# Micro.net
KiCad netlist of a schematic drawn in Altium Designer
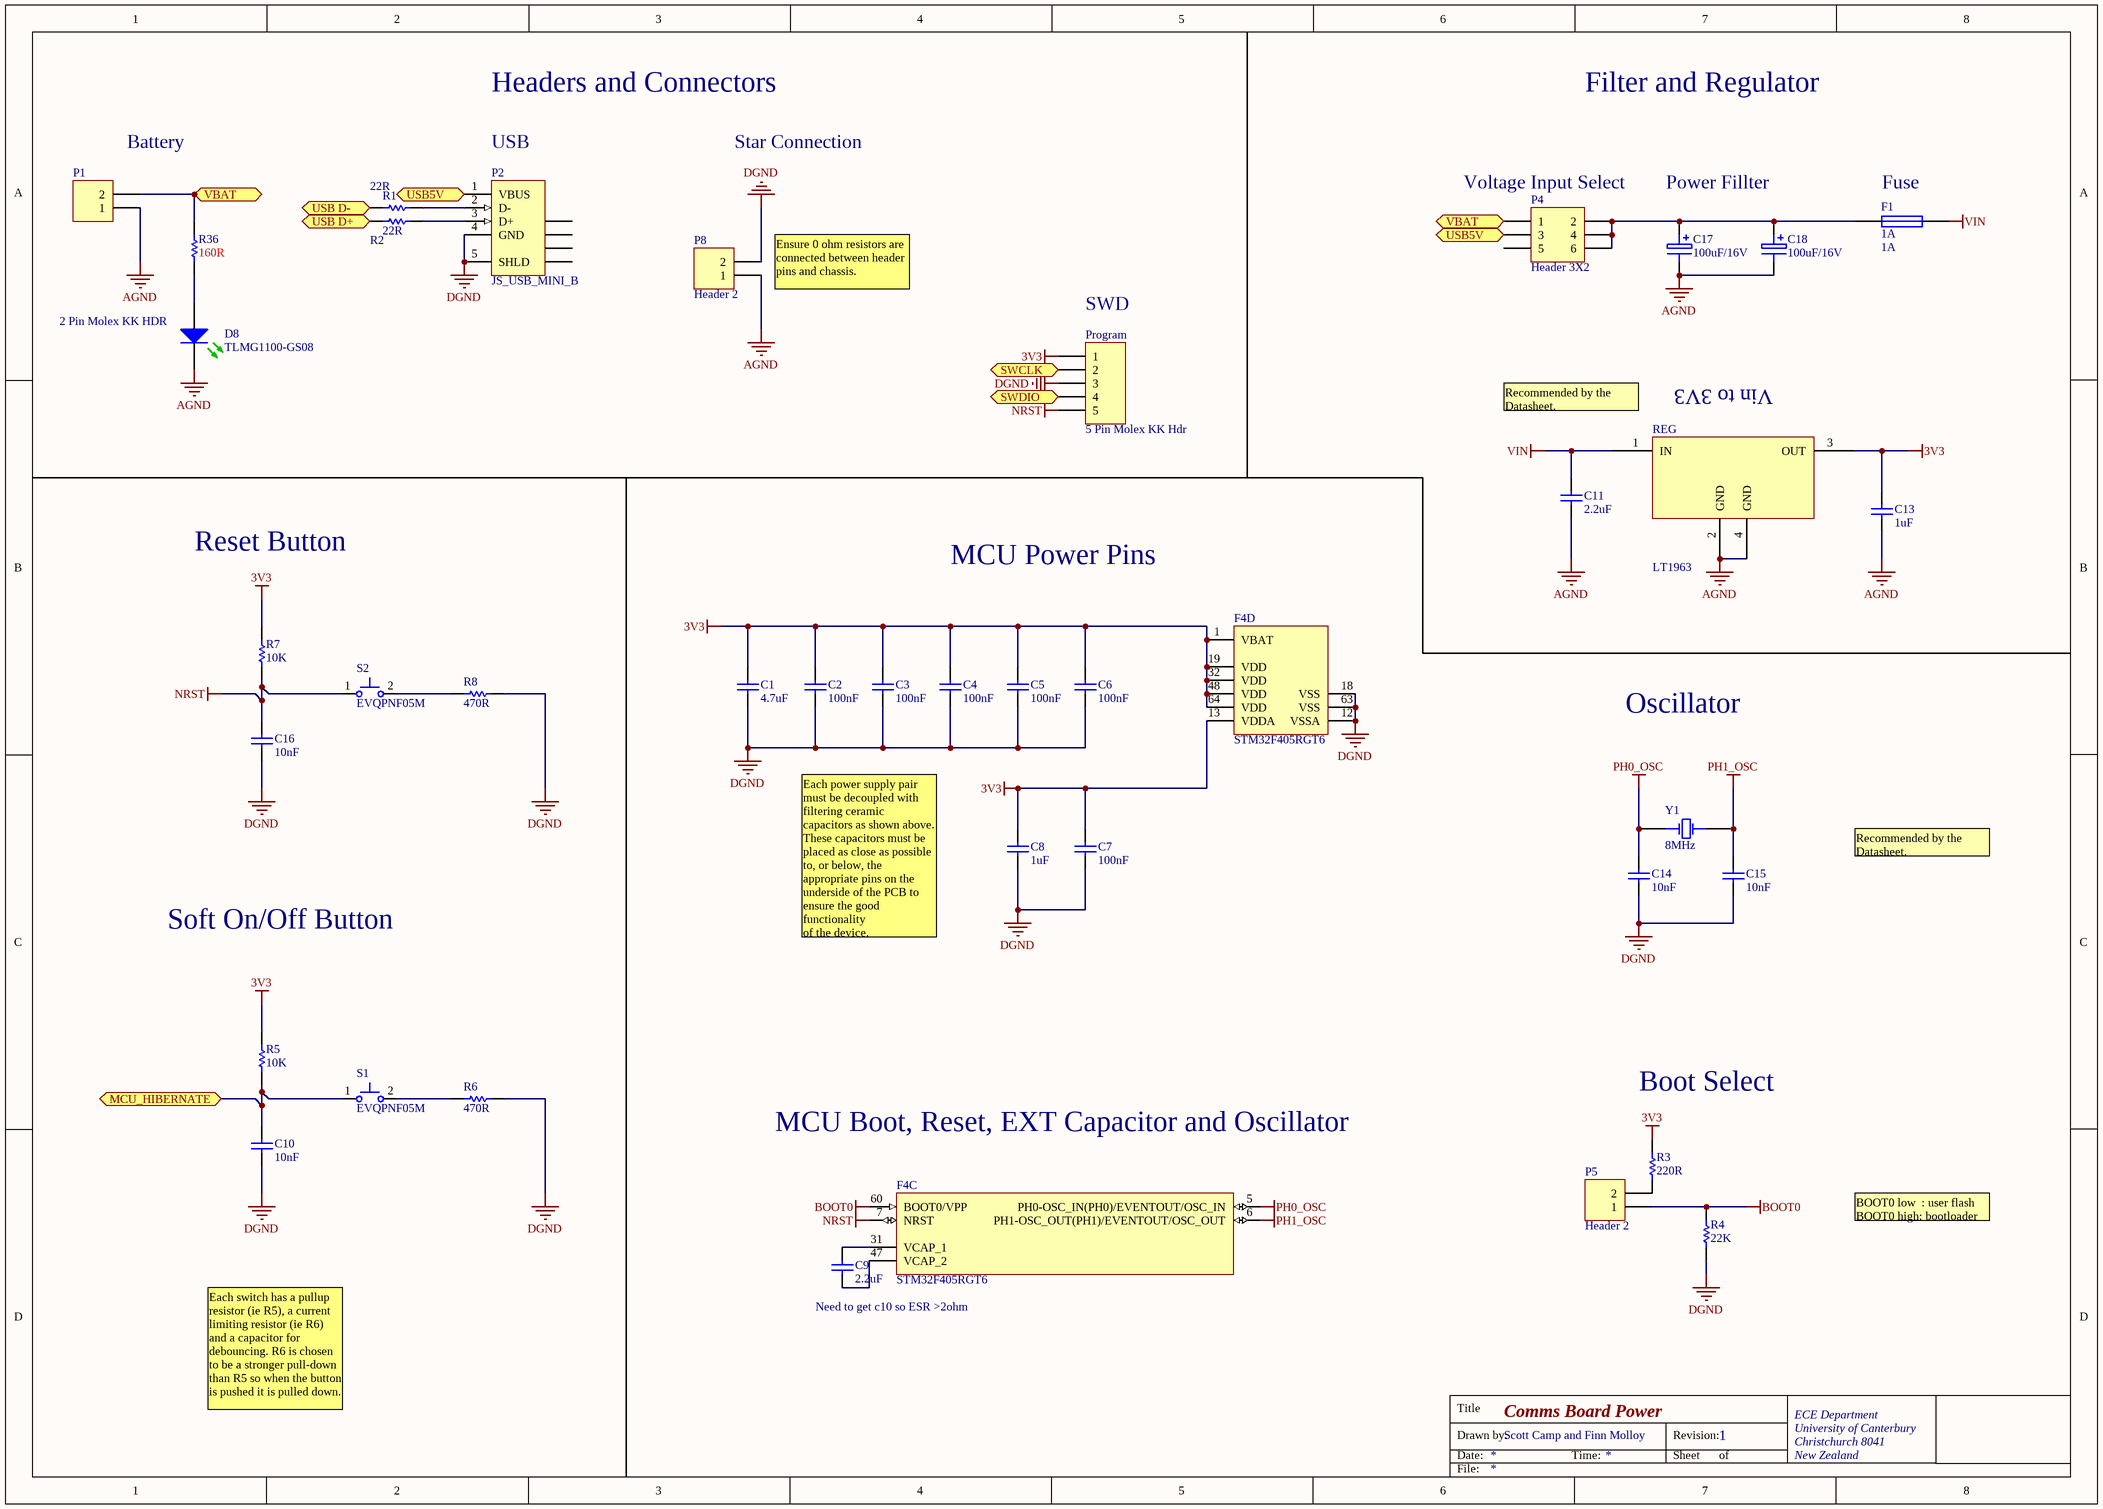
[diagram p0: Micro.SchDoc]

(export (version "E")
  (design (tool "Eeschema 10.0.6"))
  (components
    (comp (ref "C1")
      (value "4.7uF")
      (footprint "CAPC2012L")
      (description "CAP CER 4.7uF Y5V -20% +80% 16V 0805")
      (libsource (lib "ECE Components-Ver2") (part "CC_4.7uF_0805"))
    )
    (comp (ref "C2")
      (value "100nF")
      (footprint "CAPC1005L")
      (description "CAP CER 100nF X7R +-10% 16V 0402")
      (libsource (lib "ECE Components-Ver2") (part "CC_100nF_0402"))
    )
    (comp (ref "C3")
      (value "100nF")
      (footprint "CAPC1005L")
      (description "CAP CER 100nF X7R +-10% 16V 0402")
      (libsource (lib "ECE Components-Ver2") (part "CC_100nF_0402"))
    )
    (comp (ref "C4")
      (value "100nF")
      (footprint "CAPC1005L")
      (description "CAP CER 100nF X7R +-10% 16V 0402")
      (libsource (lib "ECE Components-Ver2") (part "CC_100nF_0402"))
    )
    (comp (ref "C5")
      (value "100nF")
      (footprint "CAPC1005L")
      (description "CAP CER 100nF X7R +-10% 16V 0402")
      (libsource (lib "ECE Components-Ver2") (part "CC_100nF_0402"))
    )
    (comp (ref "C6")
      (value "100nF")
      (footprint "CAPC1005L")
      (description "CAP CER 100nF X7R +-10% 16V 0402")
      (libsource (lib "ECE Components-Ver2") (part "CC_100nF_0402"))
    )
    (comp (ref "C7")
      (value "100nF")
      (footprint "CAPC1005L")
      (description "CAP CER 100nF X7R +-10% 16V 0402")
      (libsource (lib "ECE Components-Ver2") (part "CC_100nF_0402"))
    )
    (comp (ref "C8")
      (value "1uF")
      (footprint "CAPC1608L")
      (description "CAP CER 1uF Y5V -20% +80% 16V 0603")
      (libsource (lib "ECE Components-Ver2") (part "CC_1uF_0603"))
    )
    (comp (ref "C9")
      (value "2.2uF")
      (footprint "CAPC2012L")
      (description "CAP CER 2.2uF Y5V -20% +80% 25V 0805")
      (libsource (lib "ECE Components-Ver2") (part "CC_2.2uF_0805"))
    )
    (comp (ref "C10")
      (value "10nF")
      (footprint "CAPC1608L")
      (description "CAP CER 10nF X7R +-10% 50V 0603")
      (libsource (lib "ECE Components-Ver2") (part "CC_10nF_0603"))
    )
    (comp (ref "C11")
      (value "2.2uF")
      (footprint "CAPC2012L")
      (description "CAP CER 2.2uF Y5V -20% +80% 25V 0805")
      (libsource (lib "ECE Components-Ver2") (part "CC_2.2uF_0805"))
    )
    (comp (ref "C13")
      (value "1uF")
      (footprint "CAPC1608L")
      (description "CAP CER 1uF Y5V -20% +80% 16V 0603")
      (libsource (lib "ECE Components-Ver2") (part "CC_1uF_0603"))
    )
    (comp (ref "C14")
      (value "10nF")
      (footprint "CAPC1608L")
      (description "CAP CER 10nF X7R +-10% 50V 0603")
      (libsource (lib "ECE Components-Ver2") (part "CC_10nF_0603"))
    )
    (comp (ref "C15")
      (value "10nF")
      (footprint "CAPC1608L")
      (description "CAP CER 10nF X7R +-10% 50V 0603")
      (libsource (lib "ECE Components-Ver2") (part "CC_10nF_0603"))
    )
    (comp (ref "C16")
      (value "10nF")
      (footprint "CAPC1608L")
      (description "CAP CER 10nF X7R +-10% 50V 0603")
      (libsource (lib "ECE Components-Ver2") (part "CC_10nF_0603"))
    )
    (comp (ref "C17")
      (value "100uF/16V")
      (footprint "NICH-1")
      (description "Nichcon WX series  SMT Aluminium Electrolytic Cap")
      (fields (field (name "MANUFACTURER") "Nichcon"))
      (libsource (lib "ECE Components-Ver2") (part "CA_100uF_16V_SMD"))
    )
    (comp (ref "C18")
      (value "100uF/16V")
      (footprint "NICH-1")
      (description "Nichcon WX series  SMT Aluminium Electrolytic Cap")
      (fields (field (name "MANUFACTURER") "Nichcon"))
      (libsource (lib "ECE Components-Ver2") (part "CA_100uF_16V_SMD"))
    )
    (comp (ref "D8")
      (value "TLMG1100-GS08")
      (footprint "LED0.8X1.6")
      (description "LED Green 0603")
      (fields
        (field (name "MANUFACTURER") "Vishay Semiconductor Opto Division")
        (field (name "MANUFACTURER PART NUMBER") "TLMG1100-GS08")
      )
      (libsource (lib "ECE Components-Ver2") (part "DL_TLMG1100"))
    )
    (comp (ref "F1")
      (value "1A")
      (footprint "RESC3216N")
      (description "Fuse 1.0A Very Fast Acting 1206")
      (fields (field (name "MANUFACTURER") "Multicomp") (field (name "ALTIUM_VALUE") "1A"))
      (libsource (lib "ECE Components-Ver2") (part "FS_Fuse_1.0A_SMD_1206"))
    )
    (comp (ref "F4")
      (value "STM32F405RGT6")
      (footprint "TQFP64_V")
      (libsource (lib "STMicroelectronics STM32 F4") (part "STM32F405RGT6"))
    )
    (comp (ref "P1")
      (value "2 Pin Molex KK HDR")
      (footprint "MOLEX_KK_2_HDR")
      (description "CONN HEADER 2POS 2.54mm VERT_Thru Hole")
      (libsource (lib "ECE Components-Ver2") (part "JA_MOLEX_KK_2POS"))
    )
    (comp (ref "P2")
      (value "JS_USB_MINI_B")
      (footprint "USB/SM0.8-6H5")
      (description "USB 2.0, Right Angle, SMT, B Type, Receptacle, 5 Position,")
      (fields (field (name "MANUFACTURER") "FCI"))
      (libsource (lib "ECE Components-Ver2") (part "JS_USB_MINI_B_SMT"))
    )
    (comp (ref "P4")
      (value "Header 3X2")
      (footprint "HDR2X3")
      (description "Header, 3-Pin, Dual row")
      (fields (field (name "PUBLISHER") "Altium Limited"))
      (libsource (lib "Miscellaneous Connectors") (part "Header 3X2"))
    )
    (comp (ref "P5")
      (value "Header 2")
      (footprint "HDR1X2")
      (description "Header, 2-Pin")
      (fields (field (name "PUBLISHER") "Altium Limited"))
      (libsource (lib "Miscellaneous Connectors") (part "Header 2"))
    )
    (comp (ref "P8")
      (value "Header 2")
      (footprint "HDR1X2")
      (description "Header, 2-Pin")
      (fields (field (name "PUBLISHER") "Altium Limited"))
      (libsource (lib "Miscellaneous Connectors") (part "Header 2"))
    )
    (comp (ref "Program")
      (value "5 Pin Molex KK Hdr")
      (footprint "MOLEX_KK_5_HDR")
      (description "CONN HEADER 5POS 2.54mm VERT_Thru Hole")
      (fields (field (name "MANUFACTURER") "Molex"))
      (libsource (lib "ECE Components-Ver2") (part "JA_MOLEX_KK_5POS"))
    )
    (comp (ref "R1")
      (value "22R")
      (footprint "RESC1608L")
      (description "RES 22 OHM 1/10W 5% 0603 SMD")
      (libsource (lib "ECE Components-Ver2") (part "RS_22R"))
    )
    (comp (ref "R2")
      (value "22R")
      (footprint "RESC1608L")
      (description "RES 22 OHM 1/10W 5% 0603 SMD")
      (libsource (lib "ECE Components-Ver2") (part "RS_22R"))
    )
    (comp (ref "R3")
      (value "220R")
      (footprint "RESC1608L")
      (description "RES 220 OHM 1/10W 5% 0603 SMD")
      (libsource (lib "ECE Components-Ver2") (part "RS_220R"))
    )
    (comp (ref "R4")
      (value "22K")
      (footprint "RESC1608L")
      (description "RES 22.0K OHM 1/10W 5% 0603 SMD")
      (libsource (lib "ECE Components-Ver2") (part "RS_22K"))
    )
    (comp (ref "R5")
      (value "10K")
      (footprint "RESC1608L")
      (description "RES 10.0K OHM 1/10W 5% 0603 SMD")
      (libsource (lib "ECE Components-Ver2") (part "RS_10K"))
    )
    (comp (ref "R6")
      (value "470R")
      (footprint "RESC1608L")
      (description "RES 470 OHM 1/10W 5% 0603 SMD")
      (libsource (lib "ECE Components-Ver2") (part "RS_470R"))
    )
    (comp (ref "R7")
      (value "10K")
      (footprint "RESC1608L")
      (description "RES 10.0K OHM 1/10W 5% 0603 SMD")
      (libsource (lib "ECE Components-Ver2") (part "RS_10K"))
    )
    (comp (ref "R8")
      (value "470R")
      (footprint "RESC1608L")
      (description "RES 470 OHM 1/10W 5% 0603 SMD")
      (libsource (lib "ECE Components-Ver2") (part "RS_470R"))
    )
    (comp (ref "R36")
      (value "160R")
      (footprint "RESC1608L")
      (description "RES 160 OHM 1/10W 5% 0603 SMD")
      (libsource (lib "ECE Components-Ver2") (part "RS_160R"))
    )
    (comp (ref "REG") (value "LT1963") (footprint "SOT223-4M") (libsource (lib "Components") (part "LT1963")))
    (comp (ref "S1")
      (value "EVQPNF05M")
      (footprint "EVQPNF05M")
      (description "Panasonic 6 x 3.5mm SMD Light Touch Switch Type")
      (fields (field (name "MANUFACTURER") "Panasonic"))
      (libsource (lib "ECE Components-Ver2") (part "WS_EVQPNF05M"))
    )
    (comp (ref "S2")
      (value "EVQPNF05M")
      (footprint "EVQPNF05M")
      (description "Panasonic 6 x 3.5mm SMD Light Touch Switch Type")
      (fields (field (name "MANUFACTURER") "Panasonic"))
      (libsource (lib "ECE Components-Ver2") (part "WS_EVQPNF05M"))
    )
    (comp (ref "Y1")
      (value "8MHz")
      (footprint "HC49/4h_SMX")
      (description "CRYSTAL 8.00 MHZ 18PF SMD")
      (fields (field (name "MANUFACTURER") "Abracon Corporation"))
      (libsource (lib "ECE Components-Ver2") (part "XT_8MHz_HC49/4H"))
    )
  )
  (nets
    (net (code "1") (name "/MCU_HIBERNATE") (class "Default")
      (node (ref "C10") (pin "2") (pinfunction "2_2") (pintype "passive"))
      (node (ref "R5") (pin "1") (pinfunction "1_1") (pintype "passive"))
      (node (ref "S1") (pin "1") (pinfunction "1_1") (pintype "passive"))
    )
    (net (code "2") (name "/SWCLK") (class "Default")
      (node (ref "Program") (pin "2") (pinfunction "2_2") (pintype "passive"))
    )
    (net (code "3") (name "/SWDIO") (class "Default")
      (node (ref "Program") (pin "4") (pinfunction "4_4") (pintype "passive"))
    )
    (net (code "4") (name "/USB D+") (class "Default")
      (node (ref "R2") (pin "1") (pinfunction "1_1") (pintype "passive"))
    )
    (net (code "5") (name "/USB D-") (class "Default")
      (node (ref "R1") (pin "1") (pinfunction "1_1") (pintype "passive"))
    )
    (net (code "6") (name "/USB5V") (class "Default")
      (node (ref "P2") (pin "1") (pinfunction "VBUS_1") (pintype "power_in"))
      (node (ref "P4") (pin "3") (pinfunction "3_3") (pintype "passive"))
    )
    (net (code "7") (name "/VBAT") (class "Default")
      (node (ref "P1") (pin "2") (pinfunction "2_2") (pintype "passive"))
      (node (ref "P4") (pin "1") (pinfunction "1_1") (pintype "passive"))
      (node (ref "R36") (pin "2") (pinfunction "2_2") (pintype "passive"))
    )
    (net (code "8") (name "3V3") (class "Default")
      (node (ref "C1") (pin "2") (pinfunction "2_2") (pintype "passive"))
      (node (ref "C13") (pin "2") (pinfunction "2_2") (pintype "passive"))
      (node (ref "C2") (pin "2") (pinfunction "2_2") (pintype "passive"))
      (node (ref "C3") (pin "2") (pinfunction "2_2") (pintype "passive"))
      (node (ref "C4") (pin "2") (pinfunction "2_2") (pintype "passive"))
      (node (ref "C5") (pin "2") (pinfunction "2_2") (pintype "passive"))
      (node (ref "C6") (pin "2") (pinfunction "2_2") (pintype "passive"))
      (node (ref "C7") (pin "2") (pinfunction "2_2") (pintype "passive"))
      (node (ref "C8") (pin "2") (pinfunction "2_2") (pintype "passive"))
      (node (ref "F4") (pin "1") (pinfunction "VBAT_1") (pintype "power_in"))
      (node (ref "F4") (pin "13") (pinfunction "VDDA_13") (pintype "power_in"))
      (node (ref "F4") (pin "19") (pinfunction "VDD_19") (pintype "power_in"))
      (node (ref "F4") (pin "32") (pinfunction "VDD_32") (pintype "power_in"))
      (node (ref "F4") (pin "48") (pinfunction "VDD_48") (pintype "power_in"))
      (node (ref "F4") (pin "64") (pinfunction "VDD_64") (pintype "power_in"))
      (node (ref "Program") (pin "1") (pinfunction "1_1") (pintype "passive"))
      (node (ref "R3") (pin "2") (pinfunction "2_2") (pintype "passive"))
      (node (ref "R5") (pin "2") (pinfunction "2_2") (pintype "passive"))
      (node (ref "R7") (pin "2") (pinfunction "2_2") (pintype "passive"))
      (node (ref "REG") (pin "3") (pinfunction "OUT_3") (pintype "passive"))
    )
    (net (code "9") (name "AGND") (class "Default")
      (node (ref "C11") (pin "2") (pinfunction "2_2") (pintype "passive"))
      (node (ref "C13") (pin "1") (pinfunction "1_1") (pintype "passive"))
      (node (ref "C17") (pin "1") (pintype "passive"))
      (node (ref "C18") (pin "1") (pintype "passive"))
      (node (ref "D8") (pin "2") (pinfunction "K_2") (pintype "passive"))
      (node (ref "P1") (pin "1") (pinfunction "1_1") (pintype "passive"))
      (node (ref "P8") (pin "1") (pinfunction "1_1") (pintype "passive"))
      (node (ref "REG") (pin "2") (pinfunction "GND_2") (pintype "passive"))
      (node (ref "REG") (pin "4") (pinfunction "GND_4") (pintype "passive"))
    )
    (net (code "10") (name "BOOT0") (class "Default")
      (node (ref "F4") (pin "60") (pinfunction "BOOT0/VPP_60") (pintype "input"))
      (node (ref "P5") (pin "1") (pinfunction "1_1") (pintype "passive"))
      (node (ref "R4") (pin "2") (pinfunction "2_2") (pintype "passive"))
    )
    (net (code "11") (name "DGND") (class "Default")
      (node (ref "C1") (pin "1") (pinfunction "1_1") (pintype "passive"))
      (node (ref "C10") (pin "1") (pinfunction "1_1") (pintype "passive"))
      (node (ref "C14") (pin "1") (pinfunction "1_1") (pintype "passive"))
      (node (ref "C15") (pin "1") (pinfunction "1_1") (pintype "passive"))
      (node (ref "C16") (pin "1") (pinfunction "1_1") (pintype "passive"))
      (node (ref "C2") (pin "1") (pinfunction "1_1") (pintype "passive"))
      (node (ref "C3") (pin "1") (pinfunction "1_1") (pintype "passive"))
      (node (ref "C4") (pin "1") (pinfunction "1_1") (pintype "passive"))
      (node (ref "C5") (pin "1") (pinfunction "1_1") (pintype "passive"))
      (node (ref "C6") (pin "1") (pinfunction "1_1") (pintype "passive"))
      (node (ref "C7") (pin "1") (pinfunction "1_1") (pintype "passive"))
      (node (ref "C8") (pin "1") (pinfunction "1_1") (pintype "passive"))
      (node (ref "F4") (pin "12") (pinfunction "VSSA_12") (pintype "power_in"))
      (node (ref "F4") (pin "18") (pinfunction "VSS_18") (pintype "power_in"))
      (node (ref "F4") (pin "63") (pinfunction "VSS_63") (pintype "power_in"))
      (node (ref "P2") (pin "4") (pinfunction "GND_4") (pintype "power_in"))
      (node (ref "P2") (pin "5") (pinfunction "SHLD_5") (pintype "passive"))
      (node (ref "P8") (pin "2") (pinfunction "2_2") (pintype "passive"))
      (node (ref "Program") (pin "3") (pinfunction "3_3") (pintype "passive"))
      (node (ref "R4") (pin "1") (pinfunction "1_1") (pintype "passive"))
      (node (ref "R6") (pin "2") (pinfunction "2_2") (pintype "passive"))
      (node (ref "R8") (pin "2") (pinfunction "2_2") (pintype "passive"))
    )
    (net (code "12") (name "NRST") (class "Default")
      (node (ref "C16") (pin "2") (pinfunction "2_2") (pintype "passive"))
      (node (ref "F4") (pin "7") (pinfunction "NRST_7") (pintype "bidirectional"))
      (node (ref "Program") (pin "5") (pinfunction "5_5") (pintype "passive"))
      (node (ref "R7") (pin "1") (pinfunction "1_1") (pintype "passive"))
      (node (ref "S2") (pin "1") (pinfunction "1_1") (pintype "passive"))
    )
    (net (code "13") (name "Net-(C17-Pad2)") (class "Default")
      (node (ref "C17") (pin "2") (pintype "passive"))
      (node (ref "C18") (pin "2") (pintype "passive"))
      (node (ref "F1") (pin "1") (pinfunction "1_1") (pintype "passive"))
      (node (ref "P4") (pin "2") (pinfunction "2_2") (pintype "passive"))
      (node (ref "P4") (pin "4") (pinfunction "4_4") (pintype "passive"))
      (node (ref "P4") (pin "6") (pinfunction "6_6") (pintype "passive"))
    )
    (net (code "14") (name "Net-(D8-A)") (class "Default")
      (node (ref "D8") (pin "1") (pinfunction "A_1") (pintype "passive"))
      (node (ref "R36") (pin "1") (pinfunction "1_1") (pintype "passive"))
    )
    (net (code "15") (name "Net-(F4C-VCAP_1)") (class "Default")
      (node (ref "C9") (pin "1") (pinfunction "1_1") (pintype "passive"))
      (node (ref "F4") (pin "31") (pinfunction "VCAP_1_31") (pintype "power_in"))
    )
    (net (code "16") (name "Net-(F4C-VCAP_2)") (class "Default")
      (node (ref "C9") (pin "2") (pinfunction "2_2") (pintype "passive"))
      (node (ref "F4") (pin "47") (pinfunction "VCAP_2_47") (pintype "power_in"))
    )
    (net (code "17") (name "Net-(P2-D+)") (class "Default")
      (node (ref "P2") (pin "3") (pinfunction "D+_3") (pintype "input"))
      (node (ref "R2") (pin "2") (pinfunction "2_2") (pintype "passive"))
    )
    (net (code "18") (name "Net-(P2-D-)") (class "Default")
      (node (ref "P2") (pin "2") (pinfunction "D-_2") (pintype "input"))
      (node (ref "R1") (pin "2") (pinfunction "2_2") (pintype "passive"))
    )
    (net (code "19") (name "Net-(P5-Pad2)") (class "Default")
      (node (ref "P5") (pin "2") (pinfunction "2_2") (pintype "passive"))
      (node (ref "R3") (pin "1") (pinfunction "1_1") (pintype "passive"))
    )
    (net (code "20") (name "Net-(R6-Pad1)") (class "Default")
      (node (ref "R6") (pin "1") (pinfunction "1_1") (pintype "passive"))
      (node (ref "S1") (pin "2") (pinfunction "2_2") (pintype "passive"))
    )
    (net (code "21") (name "Net-(R8-Pad1)") (class "Default")
      (node (ref "R8") (pin "1") (pinfunction "1_1") (pintype "passive"))
      (node (ref "S2") (pin "2") (pinfunction "2_2") (pintype "passive"))
    )
    (net (code "22") (name "PH0_OSC") (class "Default")
      (node (ref "C14") (pin "2") (pinfunction "2_2") (pintype "passive"))
      (node (ref "F4") (pin "5") (pinfunction "PH0-OSC_IN(PH0)/EVENTOUT/OSC_IN_5") (pintype "bidirectional"))
      (node (ref "Y1") (pin "1") (pinfunction "OSC1_1") (pintype "passive"))
    )
    (net (code "23") (name "PH1_OSC") (class "Default")
      (node (ref "C15") (pin "2") (pinfunction "2_2") (pintype "passive"))
      (node (ref "F4") (pin "6") (pinfunction "PH1-OSC_OUT(PH1)/EVENTOUT/OSC_OUT_6") (pintype "bidirectional"))
      (node (ref "Y1") (pin "2") (pinfunction "OSC2_2") (pintype "passive"))
    )
    (net (code "24") (name "VIN") (class "Default")
      (node (ref "C11") (pin "1") (pinfunction "1_1") (pintype "passive"))
      (node (ref "F1") (pin "2") (pinfunction "2_2") (pintype "passive"))
      (node (ref "REG") (pin "1") (pinfunction "IN_1") (pintype "passive"))
    )
    (net (code "25") (name "unconnected-(P2-SHLD-Pad6)") (class "Default")
      (node (ref "P2") (pin "6") (pinfunction "SHLD_6") (pintype "passive"))
    )
    (net (code "26") (name "unconnected-(P2-SHLD-Pad7)") (class "Default")
      (node (ref "P2") (pin "7") (pinfunction "SHLD_7") (pintype "passive"))
    )
    (net (code "27") (name "unconnected-(P2-SHLD-Pad8)") (class "Default")
      (node (ref "P2") (pin "8") (pinfunction "SHLD_8") (pintype "passive"))
    )
    (net (code "28") (name "unconnected-(P2-SHLD-Pad9)") (class "Default")
      (node (ref "P2") (pin "9") (pinfunction "SHLD_9") (pintype "passive"))
    )
    (net (code "29") (name "unconnected-(P4-Pad5)") (class "Default")
      (node (ref "P4") (pin "5") (pinfunction "5_5") (pintype "passive"))
    )
  )
)
